# RFM69HCW_BREAKOUT.net
KiCad netlist of a schematic drawn in EAGLE
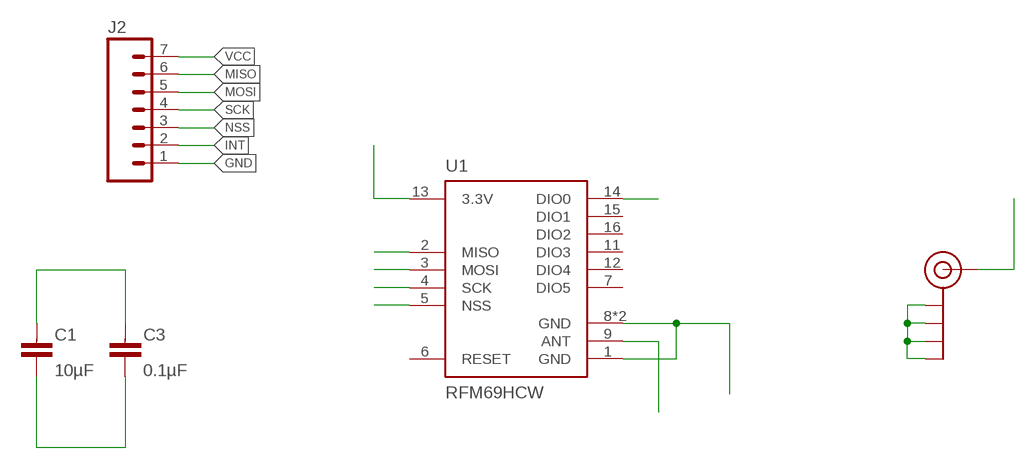
[diagram p0: schematic, sheet 1]

(export (version "E")
  (design (tool "Eeschema 10.0.6"))
  (components
    (comp (ref "C1")
      (value "10µF")
      (footprint "eagle-import:C0805-N")
      (libsource (lib "eagle-import") (part "CAPACITOR0805-N"))
    )
    (comp (ref "C3")
      (value "0.1µF")
      (footprint "eagle-import:C0603-N")
      (libsource (lib "eagle-import") (part "CAPACITOR0603-N"))
    )
    (comp (ref "J$1")
      (value "SMA_EDGE")
      (footprint "eagle-import:SMA-EDGE")
      (libsource (lib "eagle-import") (part "SMA_EDGE"))
    )
    (comp (ref "J2")
      (value "M07")
      (footprint "eagle-import:1X07")
      (libsource (lib "eagle-import") (part "M07"))
    )
    (comp (ref "U1")
      (value "RFM69HCW")
      (footprint "eagle-import:RFM69HCW-XXXS2")
      (libsource (lib "eagle-import") (part "RFM69HCW"))
    )
  )
  (nets
    (net (code "1") (name "/ANT") (class "Default")
      (node (ref "J$1") (pin "SIG") (pinfunction "SIGNAL_SIG") (pintype "bidirectional"))
      (node (ref "U1") (pin "9") (pinfunction "ANT_9") (pintype "passive"))
    )
    (net (code "2") (name "GND") (class "Default")
      (node (ref "C1") (pin "2") (pinfunction "2_2") (pintype "passive"))
      (node (ref "C3") (pin "2") (pinfunction "2_2") (pintype "passive"))
      (node (ref "J$1") (pin "GND@0") (pinfunction "GND_GND@0") (pintype "bidirectional"))
      (node (ref "J$1") (pin "GND@1") (pinfunction "GND_GND@1") (pintype "bidirectional"))
      (node (ref "J$1") (pin "GND@2") (pinfunction "GND_GND@2") (pintype "bidirectional"))
      (node (ref "J$1") (pin "GND@3") (pinfunction "GND_GND@3") (pintype "bidirectional"))
      (node (ref "J2") (pin "1") (pinfunction "1_1") (pintype "passive"))
      (node (ref "U1") (pin "1") (pinfunction "GND_1") (pintype "power_in"))
      (node (ref "U1") (pin "10") (pinfunction "GND_10") (pintype "power_in"))
      (node (ref "U1") (pin "8") (pinfunction "GND_8") (pintype "power_in"))
    )
    (net (code "3") (name "INT") (class "Default")
      (node (ref "J2") (pin "2") (pinfunction "2_2") (pintype "passive"))
      (node (ref "U1") (pin "14") (pinfunction "DIO0_14") (pintype "bidirectional"))
    )
    (net (code "4") (name "MISO") (class "Default")
      (node (ref "J2") (pin "6") (pinfunction "6_6") (pintype "passive"))
      (node (ref "U1") (pin "2") (pinfunction "MISO_2") (pintype "bidirectional"))
    )
    (net (code "5") (name "MOSI") (class "Default")
      (node (ref "J2") (pin "5") (pinfunction "5_5") (pintype "passive"))
      (node (ref "U1") (pin "3") (pinfunction "MOSI_3") (pintype "input"))
    )
    (net (code "6") (name "NSS") (class "Default")
      (node (ref "J2") (pin "3") (pinfunction "3_3") (pintype "passive"))
      (node (ref "U1") (pin "5") (pinfunction "NSS_5") (pintype "input"))
    )
    (net (code "7") (name "SCK") (class "Default")
      (node (ref "J2") (pin "4") (pinfunction "4_4") (pintype "passive"))
      (node (ref "U1") (pin "4") (pinfunction "SCK_4") (pintype "input"))
    )
    (net (code "8") (name "VCC") (class "Default")
      (node (ref "C1") (pin "1") (pinfunction "1_1") (pintype "passive"))
      (node (ref "C3") (pin "1") (pinfunction "1_1") (pintype "passive"))
      (node (ref "J2") (pin "7") (pinfunction "7_7") (pintype "passive"))
      (node (ref "U1") (pin "13") (pinfunction "3.3V_13") (pintype "power_in"))
    )
    (net (code "9") (name "unconnected-(U1-DIO1-Pad15)") (class "Default")
      (node (ref "U1") (pin "15") (pinfunction "DIO1_15") (pintype "bidirectional"))
    )
    (net (code "10") (name "unconnected-(U1-DIO2-Pad16)") (class "Default")
      (node (ref "U1") (pin "16") (pinfunction "DIO2_16") (pintype "bidirectional"))
    )
    (net (code "11") (name "unconnected-(U1-DIO3-Pad11)") (class "Default")
      (node (ref "U1") (pin "11") (pinfunction "DIO3_11") (pintype "bidirectional"))
    )
    (net (code "12") (name "unconnected-(U1-DIO4-Pad12)") (class "Default")
      (node (ref "U1") (pin "12") (pinfunction "DIO4_12") (pintype "bidirectional"))
    )
    (net (code "13") (name "unconnected-(U1-DIO5-Pad7)") (class "Default")
      (node (ref "U1") (pin "7") (pinfunction "DIO5_7") (pintype "bidirectional"))
    )
    (net (code "14") (name "unconnected-(U1-RESET-Pad6)") (class "Default")
      (node (ref "U1") (pin "6") (pinfunction "RESET_6") (pintype "input"))
    )
  )
)
